# AND_OR_XOR_NOT.net
KiCad netlist of a schematic drawn in Altium Designer
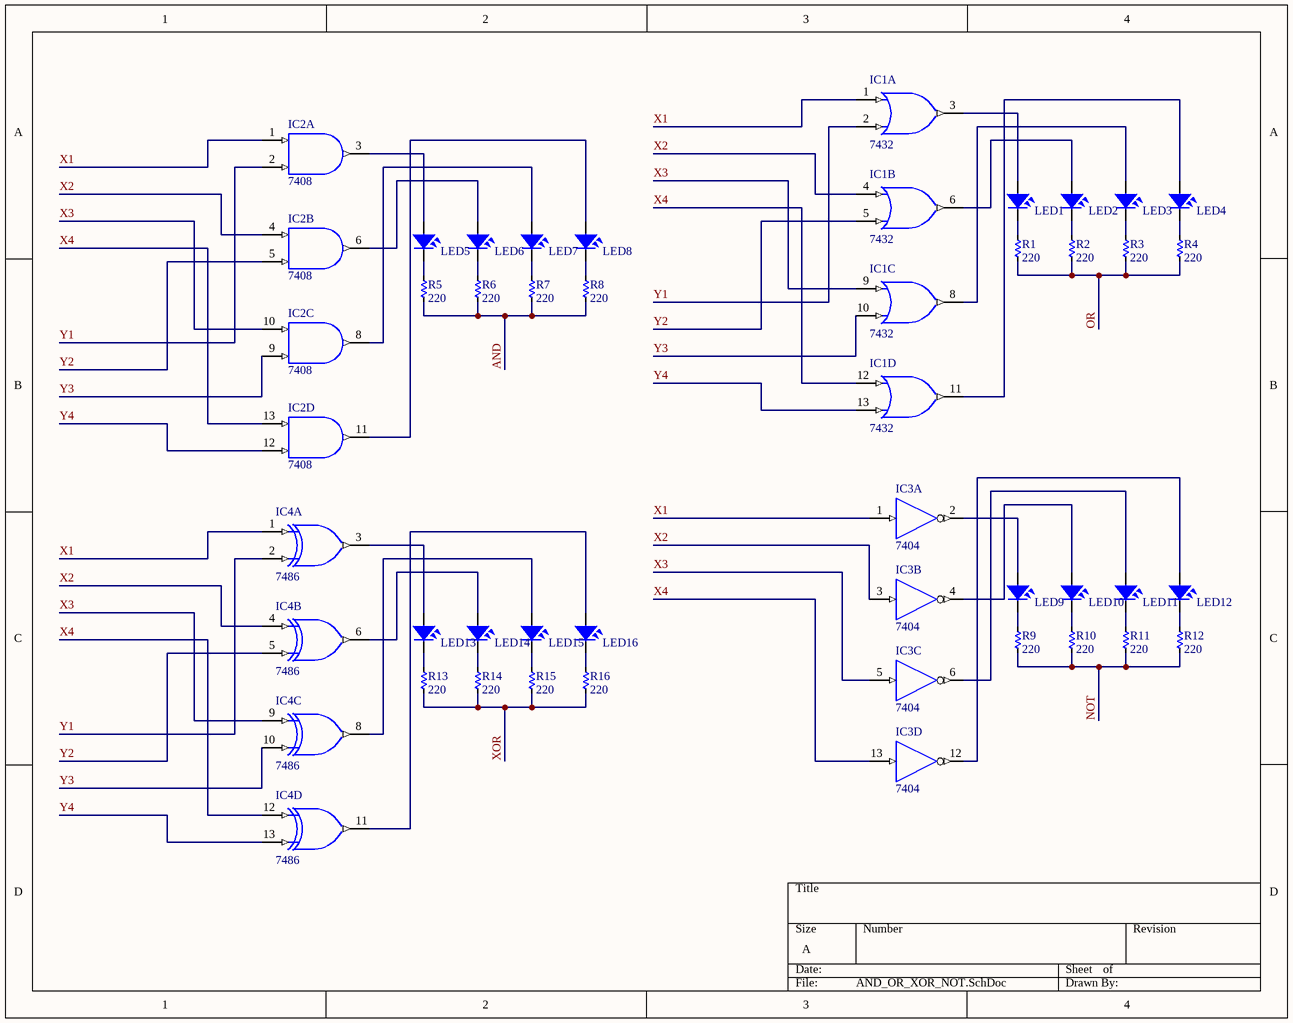
[diagram p0: AND_OR_XOR_NOT.SchDoc]

(export (version "E")
  (design (tool "Eeschema 10.0.6"))
  (components
    (comp (ref "IC1")
      (value "7432")
      (footprint "DIP14")
      (description "Quad 2-Input OR Gate")
      (libsource (lib "Schlib4bitALU") (part "7432"))
    )
    (comp (ref "IC2")
      (value "7408")
      (footprint "DIP14")
      (description "Quad 2-Input AND Gate")
      (libsource (lib "Schlib4bitALU") (part "7408"))
    )
    (comp (ref "IC3")
      (value "7404")
      (footprint "DIP14")
      (description "Hex Inverter")
      (libsource (lib "Schlib4bitALU") (part "7404"))
    )
    (comp (ref "IC4")
      (value "7486")
      (footprint "DIP14")
      (description "Quad 2-Input XOR Gate")
      (fields (field (name "COPYRIGHT BY") "VanDungEvn@Gmail.com"))
      (libsource (lib "Schlib4bitALU") (part "7486"))
    )
    (comp (ref "LED1")
      (value "LED")
      (footprint "LED-3MM-YELLOW")
      (description "LED Single colour Green and Red")
      (libsource (lib "Schlib4bitALU") (part "LED"))
    )
    (comp (ref "LED2")
      (value "LED")
      (footprint "LED-3MM-YELLOW")
      (description "LED Single colour Green and Red")
      (libsource (lib "Schlib4bitALU") (part "LED"))
    )
    (comp (ref "LED3")
      (value "LED")
      (footprint "LED-3MM-YELLOW")
      (description "LED Single colour Green and Red")
      (libsource (lib "Schlib4bitALU") (part "LED"))
    )
    (comp (ref "LED4")
      (value "LED")
      (footprint "LED-3MM-YELLOW")
      (description "LED Single colour Green and Red")
      (libsource (lib "Schlib4bitALU") (part "LED"))
    )
    (comp (ref "LED5")
      (value "LED")
      (footprint "LED-3MM-YELLOW")
      (description "LED Single colour Green and Red")
      (libsource (lib "Schlib4bitALU") (part "LED"))
    )
    (comp (ref "LED6")
      (value "LED")
      (footprint "LED-3MM-YELLOW")
      (description "LED Single colour Green and Red")
      (libsource (lib "Schlib4bitALU") (part "LED"))
    )
    (comp (ref "LED7")
      (value "LED")
      (footprint "LED-3MM-YELLOW")
      (description "LED Single colour Green and Red")
      (libsource (lib "Schlib4bitALU") (part "LED"))
    )
    (comp (ref "LED8")
      (value "LED")
      (footprint "LED-3MM-YELLOW")
      (description "LED Single colour Green and Red")
      (libsource (lib "Schlib4bitALU") (part "LED"))
    )
    (comp (ref "LED9")
      (value "LED")
      (footprint "LED-3MM-YELLOW")
      (description "LED Single colour Green and Red")
      (libsource (lib "Schlib4bitALU") (part "LED"))
    )
    (comp (ref "LED10")
      (value "LED")
      (footprint "LED-3MM-YELLOW")
      (description "LED Single colour Green and Red")
      (libsource (lib "Schlib4bitALU") (part "LED"))
    )
    (comp (ref "LED11")
      (value "LED")
      (footprint "LED-3MM-YELLOW")
      (description "LED Single colour Green and Red")
      (libsource (lib "Schlib4bitALU") (part "LED"))
    )
    (comp (ref "LED12")
      (value "LED")
      (footprint "LED-3MM-YELLOW")
      (description "LED Single colour Green and Red")
      (libsource (lib "Schlib4bitALU") (part "LED"))
    )
    (comp (ref "LED13")
      (value "LED")
      (footprint "LED-3MM-YELLOW")
      (description "LED Single colour Green and Red")
      (libsource (lib "Schlib4bitALU") (part "LED"))
    )
    (comp (ref "LED14")
      (value "LED")
      (footprint "LED-3MM-YELLOW")
      (description "LED Single colour Green and Red")
      (libsource (lib "Schlib4bitALU") (part "LED"))
    )
    (comp (ref "LED15")
      (value "LED")
      (footprint "LED-3MM-YELLOW")
      (description "LED Single colour Green and Red")
      (libsource (lib "Schlib4bitALU") (part "LED"))
    )
    (comp (ref "LED16")
      (value "LED")
      (footprint "LED-3MM-YELLOW")
      (description "LED Single colour Green and Red")
      (libsource (lib "Schlib4bitALU") (part "LED"))
    )
    (comp (ref "R1")
      (value "220")
      (footprint "RES-1/2W")
      (description "Res")
      (fields
        (field (name "MANUFACTURER") "Generic Components")
        (field (name "PUBLISHER") "Altium Hobart Technology Centre")
      )
      (libsource (lib "Schlib4bitALU") (part "Res"))
    )
    (comp (ref "R2")
      (value "220")
      (footprint "RES-1/2W")
      (description "Res")
      (fields
        (field (name "MANUFACTURER") "Generic Components")
        (field (name "PUBLISHER") "Altium Hobart Technology Centre")
      )
      (libsource (lib "Schlib4bitALU") (part "Res"))
    )
    (comp (ref "R3")
      (value "220")
      (footprint "RES-1/2W")
      (description "Res")
      (fields
        (field (name "MANUFACTURER") "Generic Components")
        (field (name "PUBLISHER") "Altium Hobart Technology Centre")
      )
      (libsource (lib "Schlib4bitALU") (part "Res"))
    )
    (comp (ref "R4")
      (value "220")
      (footprint "RES-1/2W")
      (description "Res")
      (fields
        (field (name "MANUFACTURER") "Generic Components")
        (field (name "PUBLISHER") "Altium Hobart Technology Centre")
      )
      (libsource (lib "Schlib4bitALU") (part "Res"))
    )
    (comp (ref "R5")
      (value "220")
      (footprint "RES-1/2W")
      (description "Res")
      (fields
        (field (name "MANUFACTURER") "Generic Components")
        (field (name "PUBLISHER") "Altium Hobart Technology Centre")
      )
      (libsource (lib "Schlib4bitALU") (part "Res"))
    )
    (comp (ref "R6")
      (value "220")
      (footprint "RES-1/2W")
      (description "Res")
      (fields
        (field (name "MANUFACTURER") "Generic Components")
        (field (name "PUBLISHER") "Altium Hobart Technology Centre")
      )
      (libsource (lib "Schlib4bitALU") (part "Res"))
    )
    (comp (ref "R7")
      (value "220")
      (footprint "RES-1/2W")
      (description "Res")
      (fields
        (field (name "MANUFACTURER") "Generic Components")
        (field (name "PUBLISHER") "Altium Hobart Technology Centre")
      )
      (libsource (lib "Schlib4bitALU") (part "Res"))
    )
    (comp (ref "R8")
      (value "220")
      (footprint "RES-1/2W")
      (description "Res")
      (fields
        (field (name "MANUFACTURER") "Generic Components")
        (field (name "PUBLISHER") "Altium Hobart Technology Centre")
      )
      (libsource (lib "Schlib4bitALU") (part "Res"))
    )
    (comp (ref "R9")
      (value "220")
      (footprint "RES-1/2W")
      (description "Res")
      (fields
        (field (name "MANUFACTURER") "Generic Components")
        (field (name "PUBLISHER") "Altium Hobart Technology Centre")
      )
      (libsource (lib "Schlib4bitALU") (part "Res"))
    )
    (comp (ref "R10")
      (value "220")
      (footprint "RES-1/2W")
      (description "Res")
      (fields
        (field (name "MANUFACTURER") "Generic Components")
        (field (name "PUBLISHER") "Altium Hobart Technology Centre")
      )
      (libsource (lib "Schlib4bitALU") (part "Res"))
    )
    (comp (ref "R11")
      (value "220")
      (footprint "RES-1/2W")
      (description "Res")
      (fields
        (field (name "MANUFACTURER") "Generic Components")
        (field (name "PUBLISHER") "Altium Hobart Technology Centre")
      )
      (libsource (lib "Schlib4bitALU") (part "Res"))
    )
    (comp (ref "R12")
      (value "220")
      (footprint "RES-1/2W")
      (description "Res")
      (fields
        (field (name "MANUFACTURER") "Generic Components")
        (field (name "PUBLISHER") "Altium Hobart Technology Centre")
      )
      (libsource (lib "Schlib4bitALU") (part "Res"))
    )
    (comp (ref "R13")
      (value "220")
      (footprint "RES-1/2W")
      (description "Res")
      (fields
        (field (name "MANUFACTURER") "Generic Components")
        (field (name "PUBLISHER") "Altium Hobart Technology Centre")
      )
      (libsource (lib "Schlib4bitALU") (part "Res"))
    )
    (comp (ref "R14")
      (value "220")
      (footprint "RES-1/2W")
      (description "Res")
      (fields
        (field (name "MANUFACTURER") "Generic Components")
        (field (name "PUBLISHER") "Altium Hobart Technology Centre")
      )
      (libsource (lib "Schlib4bitALU") (part "Res"))
    )
    (comp (ref "R15")
      (value "220")
      (footprint "RES-1/2W")
      (description "Res")
      (fields
        (field (name "MANUFACTURER") "Generic Components")
        (field (name "PUBLISHER") "Altium Hobart Technology Centre")
      )
      (libsource (lib "Schlib4bitALU") (part "Res"))
    )
    (comp (ref "R16")
      (value "220")
      (footprint "RES-1/2W")
      (description "Res")
      (fields
        (field (name "MANUFACTURER") "Generic Components")
        (field (name "PUBLISHER") "Altium Hobart Technology Centre")
      )
      (libsource (lib "Schlib4bitALU") (part "Res"))
    )
  )
  (nets
    (net (code "1") (name "/AND") (class "Default")
      (node (ref "R5") (pin "1") (pinfunction "1_1") (pintype "passive"))
      (node (ref "R6") (pin "1") (pinfunction "1_1") (pintype "passive"))
      (node (ref "R7") (pin "1") (pinfunction "1_1") (pintype "passive"))
      (node (ref "R8") (pin "1") (pinfunction "1_1") (pintype "passive"))
    )
    (net (code "2") (name "/NOT") (class "Default")
      (node (ref "R10") (pin "1") (pinfunction "1_1") (pintype "passive"))
      (node (ref "R11") (pin "1") (pinfunction "1_1") (pintype "passive"))
      (node (ref "R12") (pin "1") (pinfunction "1_1") (pintype "passive"))
      (node (ref "R9") (pin "1") (pinfunction "1_1") (pintype "passive"))
    )
    (net (code "3") (name "/OR") (class "Default")
      (node (ref "R1") (pin "1") (pinfunction "1_1") (pintype "passive"))
      (node (ref "R2") (pin "1") (pinfunction "1_1") (pintype "passive"))
      (node (ref "R3") (pin "1") (pinfunction "1_1") (pintype "passive"))
      (node (ref "R4") (pin "1") (pinfunction "1_1") (pintype "passive"))
    )
    (net (code "4") (name "/X1") (class "Default")
      (node (ref "IC1") (pin "1") (pinfunction "A_1") (pintype "input"))
      (node (ref "IC2") (pin "1") (pinfunction "A_1") (pintype "input"))
      (node (ref "IC3") (pin "1") (pinfunction "A_1") (pintype "input"))
      (node (ref "IC4") (pin "1") (pinfunction "A_1") (pintype "input"))
    )
    (net (code "5") (name "/X2") (class "Default")
      (node (ref "IC1") (pin "4") (pinfunction "A_4") (pintype "input"))
      (node (ref "IC2") (pin "4") (pinfunction "A_4") (pintype "input"))
      (node (ref "IC3") (pin "3") (pinfunction "A_3") (pintype "input"))
      (node (ref "IC4") (pin "4") (pinfunction "A_4") (pintype "input"))
    )
    (net (code "6") (name "/X3") (class "Default")
      (node (ref "IC1") (pin "9") (pinfunction "A_9") (pintype "input"))
      (node (ref "IC2") (pin "10") (pinfunction "A_10") (pintype "input"))
      (node (ref "IC3") (pin "5") (pinfunction "A_5") (pintype "input"))
      (node (ref "IC4") (pin "9") (pinfunction "A_9") (pintype "input"))
    )
    (net (code "7") (name "/X4") (class "Default")
      (node (ref "IC1") (pin "12") (pinfunction "A_12") (pintype "input"))
      (node (ref "IC2") (pin "13") (pinfunction "A_13") (pintype "input"))
      (node (ref "IC3") (pin "13") (pinfunction "A_13") (pintype "input"))
      (node (ref "IC4") (pin "12") (pinfunction "A_12") (pintype "input"))
    )
    (net (code "8") (name "/XOR") (class "Default")
      (node (ref "R13") (pin "1") (pinfunction "1_1") (pintype "passive"))
      (node (ref "R14") (pin "1") (pinfunction "1_1") (pintype "passive"))
      (node (ref "R15") (pin "1") (pinfunction "1_1") (pintype "passive"))
      (node (ref "R16") (pin "1") (pinfunction "1_1") (pintype "passive"))
    )
    (net (code "9") (name "/Y1") (class "Default")
      (node (ref "IC1") (pin "2") (pinfunction "B_2") (pintype "input"))
      (node (ref "IC2") (pin "2") (pinfunction "B_2") (pintype "input"))
      (node (ref "IC4") (pin "2") (pinfunction "B_2") (pintype "input"))
    )
    (net (code "10") (name "/Y2") (class "Default")
      (node (ref "IC1") (pin "5") (pinfunction "B_5") (pintype "input"))
      (node (ref "IC2") (pin "5") (pinfunction "B_5") (pintype "input"))
      (node (ref "IC4") (pin "5") (pinfunction "B_5") (pintype "input"))
    )
    (net (code "11") (name "/Y3") (class "Default")
      (node (ref "IC1") (pin "10") (pinfunction "B_10") (pintype "input"))
      (node (ref "IC2") (pin "9") (pinfunction "B_9") (pintype "input"))
      (node (ref "IC4") (pin "10") (pinfunction "B_10") (pintype "input"))
    )
    (net (code "12") (name "/Y4") (class "Default")
      (node (ref "IC1") (pin "13") (pinfunction "B_13") (pintype "input"))
      (node (ref "IC2") (pin "12") (pinfunction "B_12") (pintype "input"))
      (node (ref "IC4") (pin "13") (pinfunction "B_13") (pintype "input"))
    )
    (net (code "13") (name "GND") (class "Default")
      (node (ref "IC1") (pin "7") (pinfunction "GND_7") (pintype "power_in"))
      (node (ref "IC2") (pin "7") (pinfunction "GND_7") (pintype "power_in"))
      (node (ref "IC3") (pin "7") (pinfunction "GND_7") (pintype "power_in"))
      (node (ref "IC4") (pin "7") (pinfunction "GND_7") (pintype "power_in"))
    )
    (net (code "14") (name "Net-(IC1A-Y)") (class "Default")
      (node (ref "IC1") (pin "3") (pinfunction "Y_3") (pintype "output"))
      (node (ref "LED1") (pin "1") (pinfunction "1_1") (pintype "passive"))
    )
    (net (code "15") (name "Net-(IC1B-Y)") (class "Default")
      (node (ref "IC1") (pin "6") (pinfunction "Y_6") (pintype "output"))
      (node (ref "LED2") (pin "1") (pinfunction "1_1") (pintype "passive"))
    )
    (net (code "16") (name "Net-(IC1C-Y)") (class "Default")
      (node (ref "IC1") (pin "8") (pinfunction "Y_8") (pintype "output"))
      (node (ref "LED3") (pin "1") (pinfunction "1_1") (pintype "passive"))
    )
    (net (code "17") (name "Net-(IC1D-Y)") (class "Default")
      (node (ref "IC1") (pin "11") (pinfunction "Y_11") (pintype "output"))
      (node (ref "LED4") (pin "1") (pinfunction "1_1") (pintype "passive"))
    )
    (net (code "18") (name "Net-(IC2A-O)") (class "Default")
      (node (ref "IC2") (pin "3") (pinfunction "O_3") (pintype "output"))
      (node (ref "LED5") (pin "1") (pinfunction "1_1") (pintype "passive"))
    )
    (net (code "19") (name "Net-(IC2B-O)") (class "Default")
      (node (ref "IC2") (pin "6") (pinfunction "O_6") (pintype "output"))
      (node (ref "LED6") (pin "1") (pinfunction "1_1") (pintype "passive"))
    )
    (net (code "20") (name "Net-(IC2C-O)") (class "Default")
      (node (ref "IC2") (pin "8") (pinfunction "O_8") (pintype "output"))
      (node (ref "LED7") (pin "1") (pinfunction "1_1") (pintype "passive"))
    )
    (net (code "21") (name "Net-(IC2D-O)") (class "Default")
      (node (ref "IC2") (pin "11") (pinfunction "O_11") (pintype "output"))
      (node (ref "LED8") (pin "1") (pinfunction "1_1") (pintype "passive"))
    )
    (net (code "22") (name "Net-(IC3A-~{O})") (class "Default")
      (node (ref "IC3") (pin "2") (pinfunction "~{O}_2") (pintype "output"))
      (node (ref "LED9") (pin "1") (pinfunction "1_1") (pintype "passive"))
    )
    (net (code "23") (name "Net-(IC3B-~{O})") (class "Default")
      (node (ref "IC3") (pin "4") (pinfunction "~{O}_4") (pintype "output"))
      (node (ref "LED10") (pin "1") (pinfunction "1_1") (pintype "passive"))
    )
    (net (code "24") (name "Net-(IC3C-~{O})") (class "Default")
      (node (ref "IC3") (pin "6") (pinfunction "~{O}_6") (pintype "output"))
      (node (ref "LED11") (pin "1") (pinfunction "1_1") (pintype "passive"))
    )
    (net (code "25") (name "Net-(IC3D-~{O})") (class "Default")
      (node (ref "IC3") (pin "12") (pinfunction "~{O}_12") (pintype "output"))
      (node (ref "LED12") (pin "1") (pinfunction "1_1") (pintype "passive"))
    )
    (net (code "26") (name "Net-(IC4A-Y)") (class "Default")
      (node (ref "IC4") (pin "3") (pinfunction "Y_3") (pintype "output"))
      (node (ref "LED13") (pin "1") (pinfunction "1_1") (pintype "passive"))
    )
    (net (code "27") (name "Net-(IC4B-Y)") (class "Default")
      (node (ref "IC4") (pin "6") (pinfunction "Y_6") (pintype "output"))
      (node (ref "LED14") (pin "1") (pinfunction "1_1") (pintype "passive"))
    )
    (net (code "28") (name "Net-(IC4C-Y)") (class "Default")
      (node (ref "IC4") (pin "8") (pinfunction "Y_8") (pintype "output"))
      (node (ref "LED15") (pin "1") (pinfunction "1_1") (pintype "passive"))
    )
    (net (code "29") (name "Net-(IC4D-Y)") (class "Default")
      (node (ref "IC4") (pin "11") (pinfunction "Y_11") (pintype "output"))
      (node (ref "LED16") (pin "1") (pinfunction "1_1") (pintype "passive"))
    )
    (net (code "30") (name "Net-(LED1-Pad2)") (class "Default")
      (node (ref "LED1") (pin "2") (pinfunction "2_2") (pintype "passive"))
      (node (ref "R1") (pin "2") (pinfunction "2_2") (pintype "passive"))
    )
    (net (code "31") (name "Net-(LED2-Pad2)") (class "Default")
      (node (ref "LED2") (pin "2") (pinfunction "2_2") (pintype "passive"))
      (node (ref "R2") (pin "2") (pinfunction "2_2") (pintype "passive"))
    )
    (net (code "32") (name "Net-(LED3-Pad2)") (class "Default")
      (node (ref "LED3") (pin "2") (pinfunction "2_2") (pintype "passive"))
      (node (ref "R3") (pin "2") (pinfunction "2_2") (pintype "passive"))
    )
    (net (code "33") (name "Net-(LED4-Pad2)") (class "Default")
      (node (ref "LED4") (pin "2") (pinfunction "2_2") (pintype "passive"))
      (node (ref "R4") (pin "2") (pinfunction "2_2") (pintype "passive"))
    )
    (net (code "34") (name "Net-(LED5-Pad2)") (class "Default")
      (node (ref "LED5") (pin "2") (pinfunction "2_2") (pintype "passive"))
      (node (ref "R5") (pin "2") (pinfunction "2_2") (pintype "passive"))
    )
    (net (code "35") (name "Net-(LED6-Pad2)") (class "Default")
      (node (ref "LED6") (pin "2") (pinfunction "2_2") (pintype "passive"))
      (node (ref "R6") (pin "2") (pinfunction "2_2") (pintype "passive"))
    )
    (net (code "36") (name "Net-(LED7-Pad2)") (class "Default")
      (node (ref "LED7") (pin "2") (pinfunction "2_2") (pintype "passive"))
      (node (ref "R7") (pin "2") (pinfunction "2_2") (pintype "passive"))
    )
    (net (code "37") (name "Net-(LED8-Pad2)") (class "Default")
      (node (ref "LED8") (pin "2") (pinfunction "2_2") (pintype "passive"))
      (node (ref "R8") (pin "2") (pinfunction "2_2") (pintype "passive"))
    )
    (net (code "38") (name "Net-(LED9-Pad2)") (class "Default")
      (node (ref "LED9") (pin "2") (pinfunction "2_2") (pintype "passive"))
      (node (ref "R9") (pin "2") (pinfunction "2_2") (pintype "passive"))
    )
    (net (code "39") (name "Net-(LED10-Pad2)") (class "Default")
      (node (ref "LED10") (pin "2") (pinfunction "2_2") (pintype "passive"))
      (node (ref "R10") (pin "2") (pinfunction "2_2") (pintype "passive"))
    )
    (net (code "40") (name "Net-(LED11-Pad2)") (class "Default")
      (node (ref "LED11") (pin "2") (pinfunction "2_2") (pintype "passive"))
      (node (ref "R11") (pin "2") (pinfunction "2_2") (pintype "passive"))
    )
    (net (code "41") (name "Net-(LED12-Pad2)") (class "Default")
      (node (ref "LED12") (pin "2") (pinfunction "2_2") (pintype "passive"))
      (node (ref "R12") (pin "2") (pinfunction "2_2") (pintype "passive"))
    )
    (net (code "42") (name "Net-(LED13-Pad2)") (class "Default")
      (node (ref "LED13") (pin "2") (pinfunction "2_2") (pintype "passive"))
      (node (ref "R13") (pin "2") (pinfunction "2_2") (pintype "passive"))
    )
    (net (code "43") (name "Net-(LED14-Pad2)") (class "Default")
      (node (ref "LED14") (pin "2") (pinfunction "2_2") (pintype "passive"))
      (node (ref "R14") (pin "2") (pinfunction "2_2") (pintype "passive"))
    )
    (net (code "44") (name "Net-(LED15-Pad2)") (class "Default")
      (node (ref "LED15") (pin "2") (pinfunction "2_2") (pintype "passive"))
      (node (ref "R15") (pin "2") (pinfunction "2_2") (pintype "passive"))
    )
    (net (code "45") (name "Net-(LED16-Pad2)") (class "Default")
      (node (ref "LED16") (pin "2") (pinfunction "2_2") (pintype "passive"))
      (node (ref "R16") (pin "2") (pinfunction "2_2") (pintype "passive"))
    )
    (net (code "46") (name "VCC") (class "Default")
      (node (ref "IC1") (pin "14") (pinfunction "VCC_14") (pintype "power_in"))
      (node (ref "IC2") (pin "14") (pinfunction "VCC_14") (pintype "power_in"))
      (node (ref "IC3") (pin "14") (pinfunction "VCC_14") (pintype "power_in"))
    )
    (net (code "47") (name "VDD") (class "Default")
      (node (ref "IC4") (pin "14") (pinfunction "VDD_14") (pintype "power_in"))
    )
  )
)
